# TC1508.net
KiCad netlist of a schematic drawn in Altium Designer
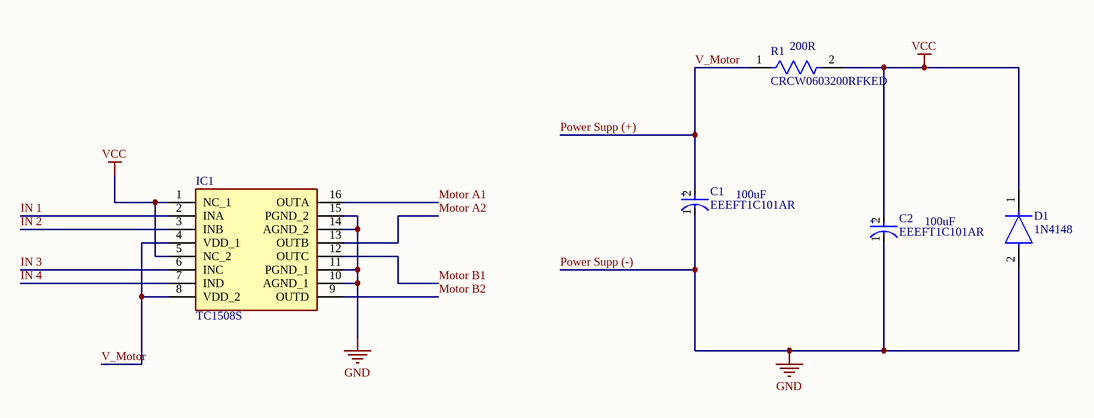
[diagram p0: TC1508.SchDoc]

(export (version "E")
  (design (tool "Eeschema 10.0.6"))
  (components
    (comp (ref "C1")
      (value "EEEFT1C101AR")
      (footprint "FP-FTC-MFG")
      (description "CAP ALUM 100UF 20% 16V SMD")
      (fields
        (field (name "CAPACITANCE") "100uF")
        (field (name "TOLERANCE") "20%")
        (field (name "VOLTAGE") "16V")
      )
      (libsource (lib "Altium Content Vault") (part "a00bbbee19879c290e62620ae7e47b1"))
    )
    (comp (ref "C2")
      (value "EEEFT1C101AR")
      (footprint "FP-FTC-MFG")
      (description "CAP ALUM 100UF 20% 16V SMD")
      (fields
        (field (name "CAPACITANCE") "100uF")
        (field (name "TOLERANCE") "20%")
        (field (name "VOLTAGE") "16V")
      )
      (libsource (lib "Altium Content Vault") (part "a00bbbee19879c290e62620ae7e47b1"))
    )
    (comp (ref "D1")
      (value "1N4148")
      (footprint "FP-017AG-MFG")
      (description "DIODE GEN PURP 100V 200MA DO35")
      (fields (field (name "VOLTAGE") "100V"))
      (libsource (lib "Altium Content Vault") (part "d7152d700b627762746794eb795d46e"))
    )
    (comp (ref "IC1")
      (value "TC1508S")
      (footprint "SamacSys:SOIC127P600X180-16N")
      (description "Integrated Circuit")
      (libsource (lib "*") (part "TC1508S"))
    )
    (comp (ref "R1")
      (value "CRCW0603200RFKED")
      (footprint "FP-CRCW0603-e3-MFG")
      (description "RES Thick Film, 200Ω, 1%, 0.1W, 100ppm/°C, 0603")
      (fields (field (name "TOLERANCE") "1%") (field (name "RESISTANCE") "200R"))
      (libsource (lib "Altium Content Vault") (part "1029c3af85768c4190bb7ad29bc67b5"))
    )
  )
  (nets
    (net (code "1") (name "/IN 1") (class "Default")
      (node (ref "IC1") (pin "2") (pinfunction "INA_2") (pintype "passive"))
    )
    (net (code "2") (name "/IN 2") (class "Default")
      (node (ref "IC1") (pin "3") (pinfunction "INB_3") (pintype "passive"))
    )
    (net (code "3") (name "/IN 3") (class "Default")
      (node (ref "IC1") (pin "6") (pinfunction "INC_6") (pintype "passive"))
    )
    (net (code "4") (name "/IN 4") (class "Default")
      (node (ref "IC1") (pin "7") (pinfunction "IND_7") (pintype "passive"))
    )
    (net (code "5") (name "/Motor A1") (class "Default")
      (node (ref "IC1") (pin "16") (pinfunction "OUTA_16") (pintype "passive"))
    )
    (net (code "6") (name "/Motor A2") (class "Default")
      (node (ref "IC1") (pin "13") (pinfunction "OUTB_13") (pintype "passive"))
    )
    (net (code "7") (name "/Motor B1") (class "Default")
      (node (ref "IC1") (pin "12") (pinfunction "OUTC_12") (pintype "passive"))
    )
    (net (code "8") (name "/Motor B2") (class "Default")
      (node (ref "IC1") (pin "9") (pinfunction "OUTD_9") (pintype "passive"))
    )
    (net (code "9") (name "/Power Supp (+)") (class "Default")
      (node (ref "C1") (pin "2") (pinfunction "A_2") (pintype "passive"))
      (node (ref "IC1") (pin "4") (pinfunction "VDD_1_4") (pintype "passive"))
      (node (ref "IC1") (pin "8") (pinfunction "VDD_2_8") (pintype "passive"))
      (node (ref "R1") (pin "1") (pinfunction "1_1") (pintype "passive"))
    )
    (net (code "10") (name "GND") (class "Default")
      (node (ref "C1") (pin "1") (pinfunction "C_1") (pintype "passive"))
      (node (ref "C2") (pin "1") (pinfunction "C_1") (pintype "passive"))
      (node (ref "D1") (pin "2") (pinfunction "A_2") (pintype "passive"))
      (node (ref "IC1") (pin "10") (pinfunction "AGND_1_10") (pintype "passive"))
      (node (ref "IC1") (pin "11") (pinfunction "PGND_1_11") (pintype "passive"))
      (node (ref "IC1") (pin "14") (pinfunction "AGND_2_14") (pintype "passive"))
      (node (ref "IC1") (pin "15") (pinfunction "PGND_2_15") (pintype "passive"))
    )
    (net (code "11") (name "VCC") (class "Default")
      (node (ref "C2") (pin "2") (pinfunction "A_2") (pintype "passive"))
      (node (ref "D1") (pin "1") (pinfunction "C_1") (pintype "passive"))
      (node (ref "IC1") (pin "1") (pinfunction "NC_1_1") (pintype "passive"))
      (node (ref "IC1") (pin "5") (pinfunction "NC_2_5") (pintype "passive"))
      (node (ref "R1") (pin "2") (pinfunction "2_2") (pintype "passive"))
    )
  )
)
